# InstrumentationAmplifier.net
KiCad netlist of a schematic drawn in EAGLE
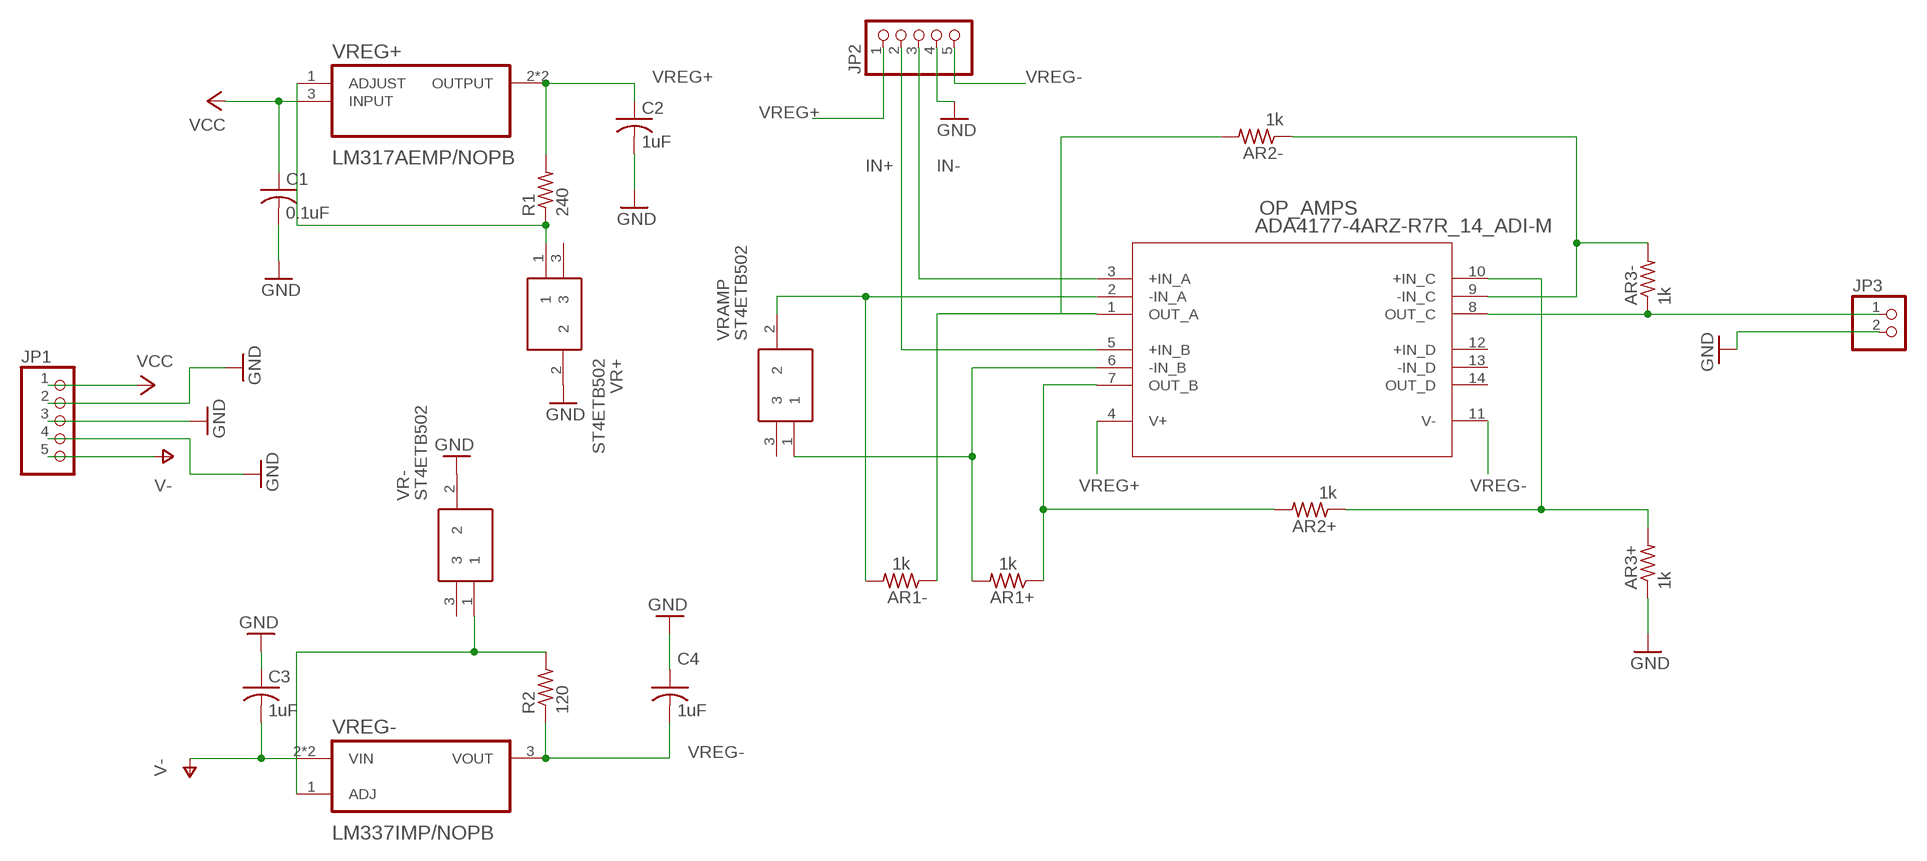
[diagram p0: schematic, sheet 1]

(export (version "E")
  (design (tool "Eeschema 10.0.6"))
  (components
    (comp (ref "AR1+")
      (value "1k")
      (footprint "eagle-import:R0603")
      (libsource (lib "eagle-import") (part "R-US_R0603"))
    )
    (comp (ref "AR1-")
      (value "1k")
      (footprint "eagle-import:R0603")
      (libsource (lib "eagle-import") (part "R-US_R0603"))
    )
    (comp (ref "AR2+")
      (value "1k")
      (footprint "eagle-import:R0603")
      (libsource (lib "eagle-import") (part "R-US_R0603"))
    )
    (comp (ref "AR2-")
      (value "1k")
      (footprint "eagle-import:R0603")
      (libsource (lib "eagle-import") (part "R-US_R0603"))
    )
    (comp (ref "AR3+")
      (value "1k")
      (footprint "eagle-import:R0603")
      (libsource (lib "eagle-import") (part "R-US_R0603"))
    )
    (comp (ref "AR3-")
      (value "1k")
      (footprint "eagle-import:R0603")
      (libsource (lib "eagle-import") (part "R-US_R0603"))
    )
    (comp (ref "C1")
      (value "0.1uF")
      (footprint "eagle-import:C0603")
      (libsource (lib "eagle-import") (part "C-USC0603"))
    )
    (comp (ref "C2")
      (value "1uF")
      (footprint "eagle-import:C0603")
      (libsource (lib "eagle-import") (part "C-USC0603"))
    )
    (comp (ref "C3")
      (value "1uF")
      (footprint "eagle-import:C0603")
      (libsource (lib "eagle-import") (part "C-USC0603"))
    )
    (comp (ref "C4")
      (value "1uF")
      (footprint "eagle-import:C0603")
      (libsource (lib "eagle-import") (part "C-USC0603"))
    )
    (comp (ref "JP1")
      (value "PINHD-1X55X2MM")
      (footprint "eagle-import:1_05X2MM")
      (libsource (lib "eagle-import") (part "PINHD-1X55X2MM"))
    )
    (comp (ref "JP2")
      (value "PINHD-1X55X2MM")
      (footprint "eagle-import:1_05X2MM")
      (libsource (lib "eagle-import") (part "PINHD-1X55X2MM"))
    )
    (comp (ref "JP3")
      (value "PINHD-1X2")
      (footprint "eagle-import:1X02")
      (libsource (lib "eagle-import") (part "PINHD-1X2"))
    )
    (comp (ref "OP_AMPS")
      (value "ADA4177-4ARZ-R7R_14_ADI-M")
      (footprint "eagle-import:R_14_ADI-M")
      (fields (field (name "MANUFACTURER_PART_NUMBER") "ADA4177-4ARZ-R7"))
      (libsource (lib "eagle-import") (part "ADA4177-4ARZ-R7R_14_ADI-M"))
    )
    (comp (ref "R1")
      (value "240")
      (footprint "eagle-import:R0603")
      (libsource (lib "eagle-import") (part "R-US_R0603"))
    )
    (comp (ref "R2")
      (value "120")
      (footprint "eagle-import:R0603")
      (libsource (lib "eagle-import") (part "R-US_R0603"))
    )
    (comp (ref "VR+")
      (value "ST4ETB502")
      (footprint "eagle-import:ST-4EB")
      (libsource (lib "eagle-import") (part "ST4ETB502"))
    )
    (comp (ref "VR-")
      (value "ST4ETB502")
      (footprint "eagle-import:ST-4EB")
      (libsource (lib "eagle-import") (part "ST4ETB502"))
    )
    (comp (ref "VRAMP")
      (value "ST4ETB502")
      (footprint "eagle-import:ST-4EB")
      (libsource (lib "eagle-import") (part "ST4ETB502"))
    )
    (comp (ref "VREG+")
      (value "LM317AEMP/NOPB")
      (footprint "eagle-import:SOT230P700X180-4N")
      (fields
        (field (name "DIGI-KEY_PART_NUMBER") "LM317AEMPCT-ND")
        (field (name "MF") "Texas Instruments")
        (field (name "MP") "LM317AEMP")
      )
      (libsource (lib "eagle-import") (part "LM317AEMP/NOPB"))
    )
    (comp (ref "VREG-")
      (value "LM337IMP/NOPB")
      (footprint "eagle-import:SOT230P700X180-4N")
      (fields
        (field (name "DIGI-KEY_PART_NUMBER") "LM337IMPCT-ND")
        (field (name "MF") "Texas Instruments")
        (field (name "MP") "LM337IMP")
      )
      (libsource (lib "eagle-import") (part "LM337IMP/NOPB"))
    )
  )
  (nets
    (net (code "1") (name "/IN+") (class "Default")
      (node (ref "JP2") (pin "2") (pinfunction "2_2") (pintype "passive"))
      (node (ref "OP_AMPS") (pin "5") (pinfunction "+IN_B_5") (pintype "passive"))
    )
    (net (code "2") (name "/IN-") (class "Default")
      (node (ref "JP2") (pin "3") (pinfunction "3_3") (pintype "passive"))
      (node (ref "OP_AMPS") (pin "3") (pinfunction "+IN_A_3") (pintype "passive"))
    )
    (net (code "3") (name "/VREG+") (class "Default")
      (node (ref "C2") (pin "1") (pinfunction "1_1") (pintype "passive"))
      (node (ref "JP2") (pin "1") (pinfunction "1_1") (pintype "passive"))
      (node (ref "OP_AMPS") (pin "4") (pinfunction "V+_4") (pintype "passive"))
      (node (ref "R1") (pin "2") (pinfunction "2_2") (pintype "passive"))
      (node (ref "VREG+") (pin "2") (pinfunction "OUTPUT_2") (pintype "output"))
      (node (ref "VREG+") (pin "4") (pinfunction "OUTPUT_4") (pintype "output"))
    )
    (net (code "4") (name "/VREG-") (class "Default")
      (node (ref "C4") (pin "2") (pinfunction "2_2") (pintype "passive"))
      (node (ref "JP2") (pin "5") (pinfunction "5_5") (pintype "passive"))
      (node (ref "OP_AMPS") (pin "11") (pinfunction "V-_11") (pintype "passive"))
      (node (ref "R2") (pin "1") (pinfunction "1_1") (pintype "passive"))
      (node (ref "VREG-") (pin "3") (pinfunction "VOUT_3") (pintype "output"))
    )
    (net (code "5") (name "GND") (class "Default")
      (node (ref "AR3+") (pin "1") (pinfunction "1_1") (pintype "passive"))
      (node (ref "C1") (pin "2") (pinfunction "2_2") (pintype "passive"))
      (node (ref "C2") (pin "2") (pinfunction "2_2") (pintype "passive"))
      (node (ref "C3") (pin "1") (pinfunction "1_1") (pintype "passive"))
      (node (ref "C4") (pin "1") (pinfunction "1_1") (pintype "passive"))
      (node (ref "JP1") (pin "2") (pinfunction "2_2") (pintype "passive"))
      (node (ref "JP1") (pin "3") (pinfunction "3_3") (pintype "passive"))
      (node (ref "JP1") (pin "4") (pinfunction "4_4") (pintype "passive"))
      (node (ref "JP2") (pin "4") (pinfunction "4_4") (pintype "passive"))
      (node (ref "JP3") (pin "2") (pinfunction "2_2") (pintype "passive"))
      (node (ref "VR+") (pin "2") (pinfunction "2_2") (pintype "bidirectional"))
      (node (ref "VR-") (pin "2") (pinfunction "2_2") (pintype "bidirectional"))
    )
    (net (code "6") (name "Net-(OP_AMPS-+IN_C)") (class "Default")
      (node (ref "AR2+") (pin "1") (pinfunction "1_1") (pintype "passive"))
      (node (ref "AR3+") (pin "2") (pinfunction "2_2") (pintype "passive"))
      (node (ref "OP_AMPS") (pin "10") (pinfunction "+IN_C_10") (pintype "passive"))
    )
    (net (code "7") (name "Net-(OP_AMPS--IN_A)") (class "Default")
      (node (ref "AR1-") (pin "2") (pinfunction "2_2") (pintype "passive"))
      (node (ref "OP_AMPS") (pin "2") (pinfunction "-IN_A_2") (pintype "passive"))
      (node (ref "VRAMP") (pin "2") (pinfunction "2_2") (pintype "bidirectional"))
    )
    (net (code "8") (name "Net-(OP_AMPS--IN_B)") (class "Default")
      (node (ref "AR1+") (pin "2") (pinfunction "2_2") (pintype "passive"))
      (node (ref "OP_AMPS") (pin "6") (pinfunction "-IN_B_6") (pintype "passive"))
      (node (ref "VRAMP") (pin "1") (pinfunction "1_1") (pintype "bidirectional"))
    )
    (net (code "9") (name "Net-(OP_AMPS--IN_C)") (class "Default")
      (node (ref "AR2-") (pin "1") (pinfunction "1_1") (pintype "passive"))
      (node (ref "AR3-") (pin "2") (pinfunction "2_2") (pintype "passive"))
      (node (ref "OP_AMPS") (pin "9") (pinfunction "-IN_C_9") (pintype "passive"))
    )
    (net (code "10") (name "Net-(OP_AMPS-OUT_A)") (class "Default")
      (node (ref "AR1-") (pin "1") (pinfunction "1_1") (pintype "passive"))
      (node (ref "AR2-") (pin "2") (pinfunction "2_2") (pintype "passive"))
      (node (ref "OP_AMPS") (pin "1") (pinfunction "OUT_A_1") (pintype "passive"))
    )
    (net (code "11") (name "Net-(OP_AMPS-OUT_B)") (class "Default")
      (node (ref "AR1+") (pin "1") (pinfunction "1_1") (pintype "passive"))
      (node (ref "AR2+") (pin "2") (pinfunction "2_2") (pintype "passive"))
      (node (ref "OP_AMPS") (pin "7") (pinfunction "OUT_B_7") (pintype "passive"))
    )
    (net (code "12") (name "Net-(OP_AMPS-OUT_C)") (class "Default")
      (node (ref "AR3-") (pin "1") (pinfunction "1_1") (pintype "passive"))
      (node (ref "JP3") (pin "1") (pinfunction "1_1") (pintype "passive"))
      (node (ref "OP_AMPS") (pin "8") (pinfunction "OUT_C_8") (pintype "passive"))
    )
    (net (code "13") (name "Net-(VREG+-ADJUST)") (class "Default")
      (node (ref "R1") (pin "1") (pinfunction "1_1") (pintype "passive"))
      (node (ref "VR+") (pin "1") (pinfunction "1_1") (pintype "bidirectional"))
      (node (ref "VREG+") (pin "1") (pinfunction "ADJUST_1") (pintype "input"))
    )
    (net (code "14") (name "Net-(VREG--ADJ)") (class "Default")
      (node (ref "R2") (pin "2") (pinfunction "2_2") (pintype "passive"))
      (node (ref "VR-") (pin "1") (pinfunction "1_1") (pintype "bidirectional"))
      (node (ref "VREG-") (pin "1") (pinfunction "ADJ_1") (pintype "bidirectional"))
    )
    (net (code "15") (name "V-") (class "Default")
      (node (ref "C3") (pin "2") (pinfunction "2_2") (pintype "passive"))
      (node (ref "JP1") (pin "5") (pinfunction "5_5") (pintype "passive"))
      (node (ref "VREG-") (pin "2") (pinfunction "VIN_2") (pintype "input"))
      (node (ref "VREG-") (pin "4") (pinfunction "VIN_4") (pintype "input"))
    )
    (net (code "16") (name "VCC") (class "Default")
      (node (ref "C1") (pin "1") (pinfunction "1_1") (pintype "passive"))
      (node (ref "JP1") (pin "1") (pinfunction "1_1") (pintype "passive"))
      (node (ref "VREG+") (pin "3") (pinfunction "INPUT_3") (pintype "input"))
    )
    (net (code "17") (name "unconnected-(OP_AMPS-+IN_D-Pad12)") (class "Default")
      (node (ref "OP_AMPS") (pin "12") (pinfunction "+IN_D_12") (pintype "passive"))
    )
    (net (code "18") (name "unconnected-(OP_AMPS--IN_D-Pad13)") (class "Default")
      (node (ref "OP_AMPS") (pin "13") (pinfunction "-IN_D_13") (pintype "passive"))
    )
    (net (code "19") (name "unconnected-(OP_AMPS-OUT_D-Pad14)") (class "Default")
      (node (ref "OP_AMPS") (pin "14") (pinfunction "OUT_D_14") (pintype "passive"))
    )
    (net (code "20") (name "unconnected-(VR+-Pad3)") (class "Default")
      (node (ref "VR+") (pin "3") (pinfunction "3_3") (pintype "bidirectional"))
    )
    (net (code "21") (name "unconnected-(VR--Pad3)") (class "Default")
      (node (ref "VR-") (pin "3") (pinfunction "3_3") (pintype "bidirectional"))
    )
    (net (code "22") (name "unconnected-(VRAMP-Pad3)") (class "Default")
      (node (ref "VRAMP") (pin "3") (pinfunction "3_3") (pintype "bidirectional"))
    )
  )
)
